# powerblade_test.net
KiCad netlist of a schematic drawn in EAGLE
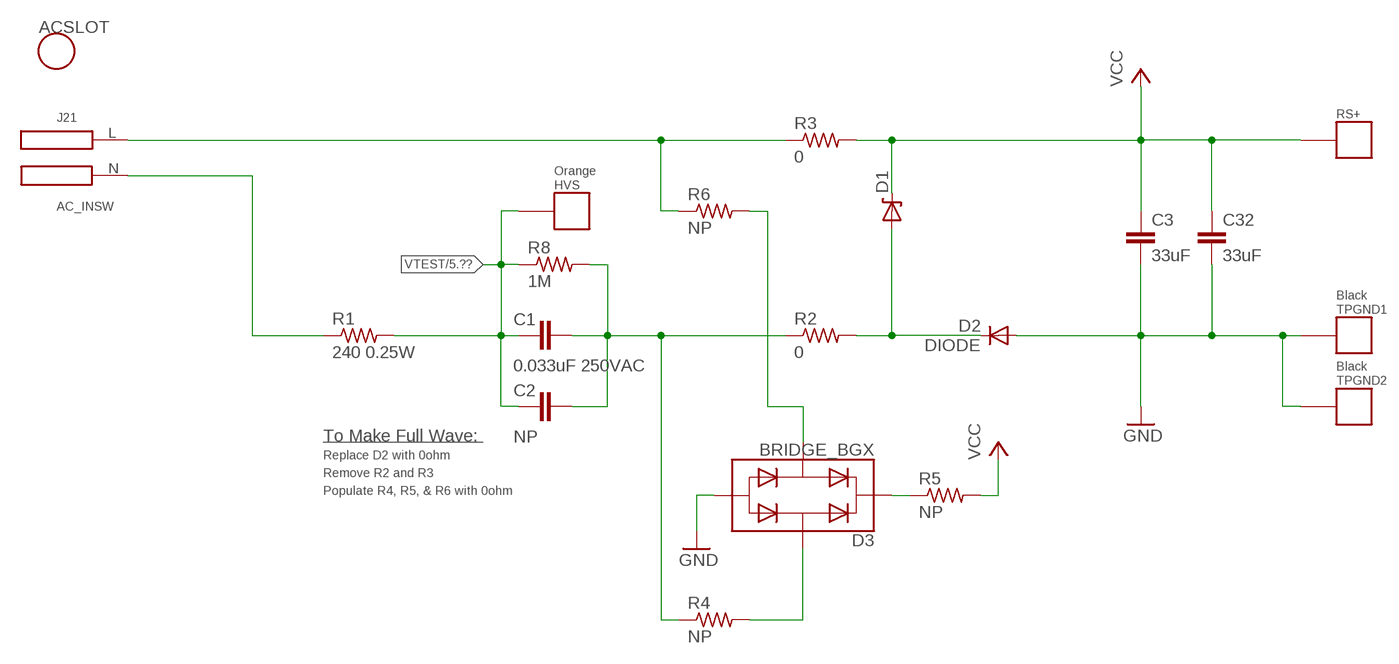
[diagram p0: schematic, sheet 1]
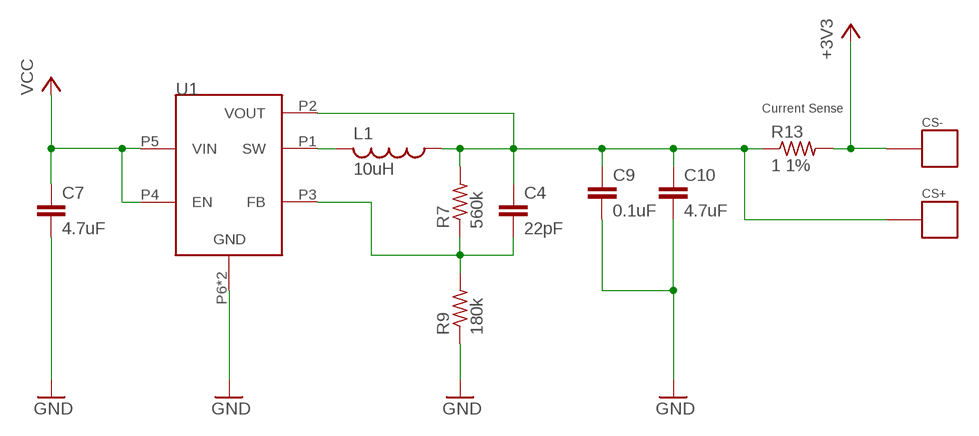
[diagram p1: schematic, sheet 2]
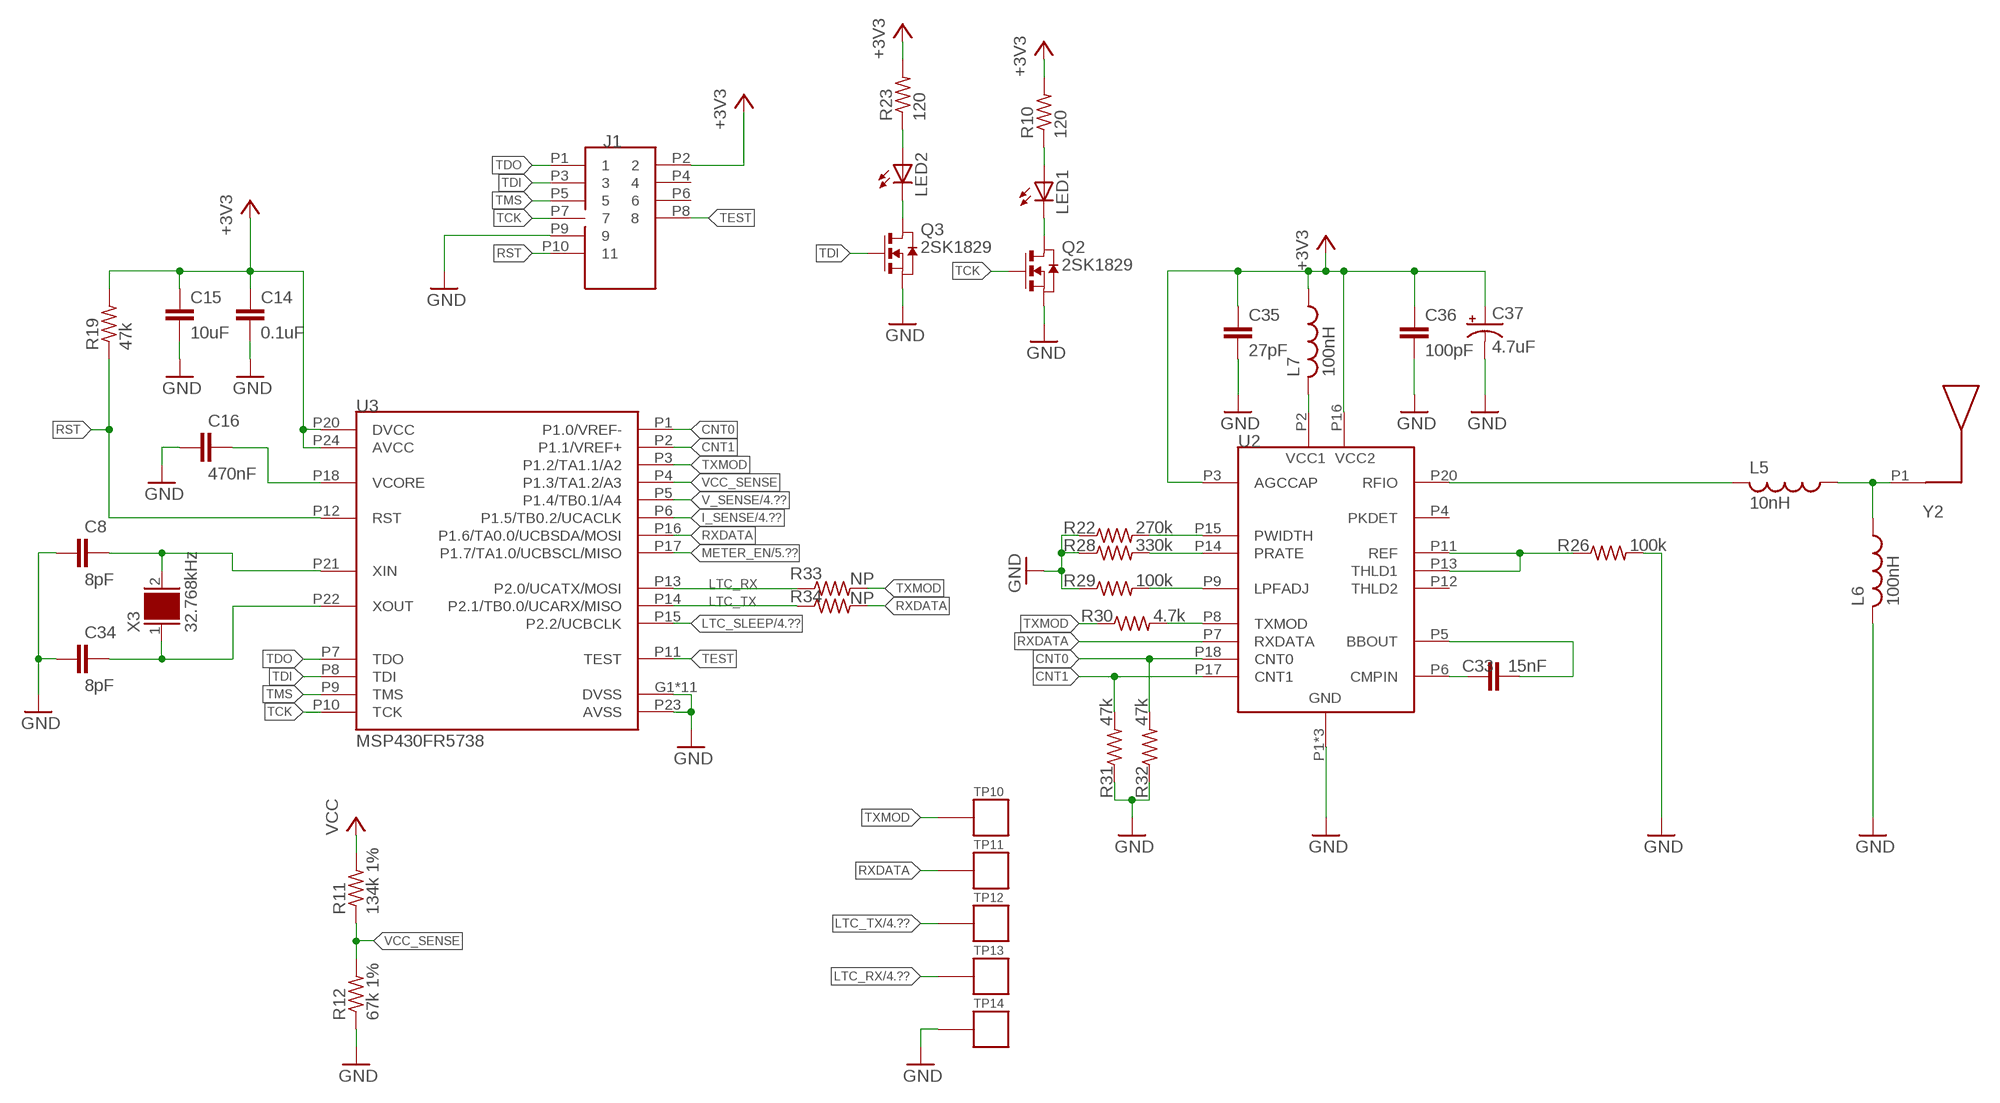
[diagram p2: schematic, sheet 3]
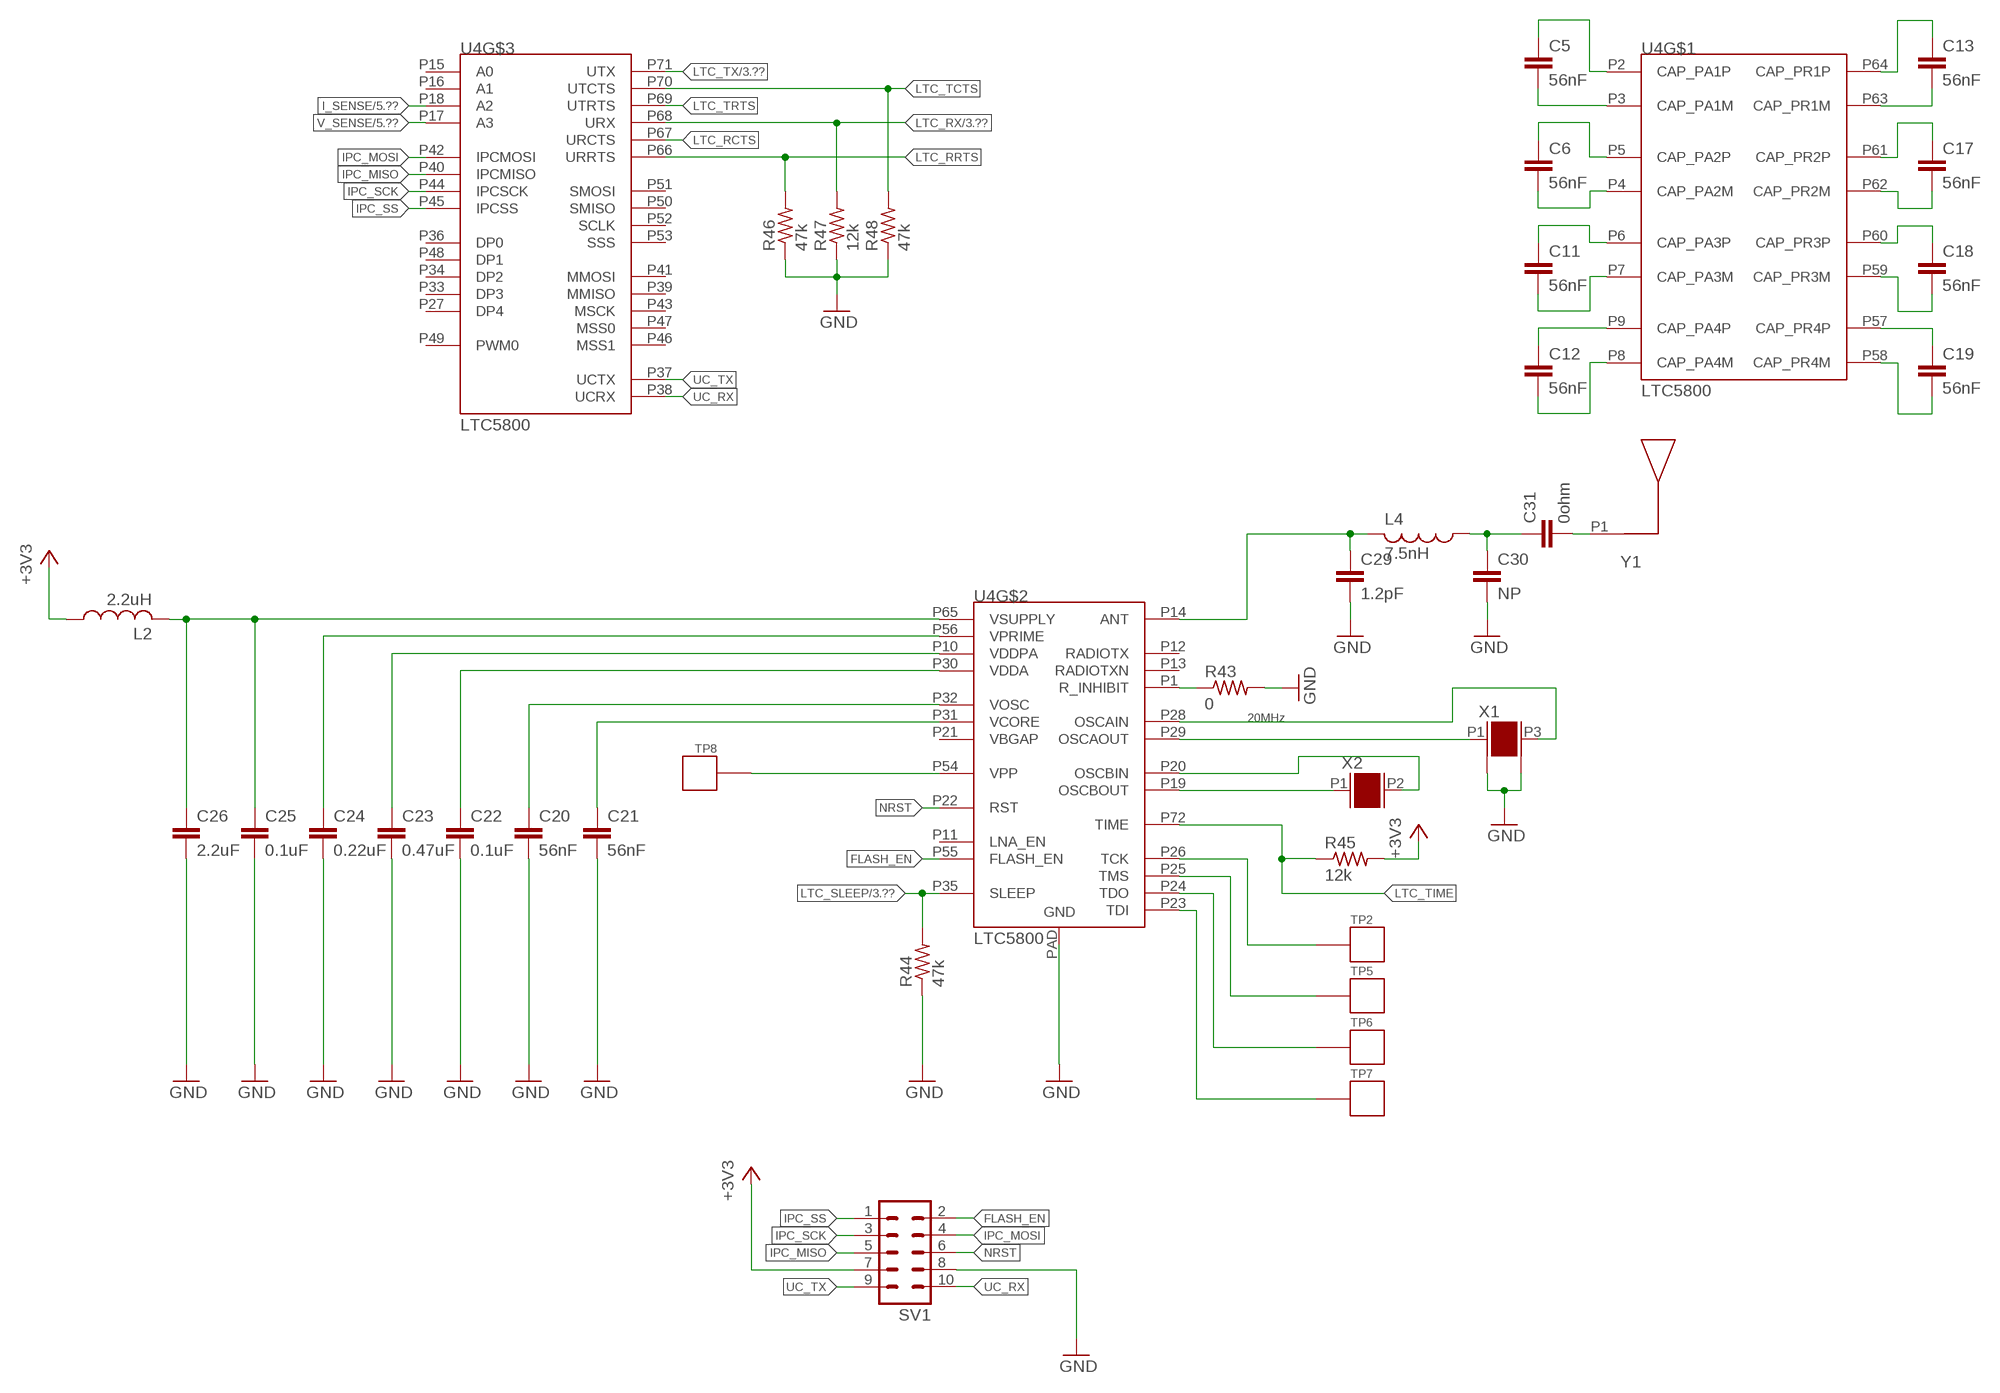
[diagram p3: schematic, sheet 4]
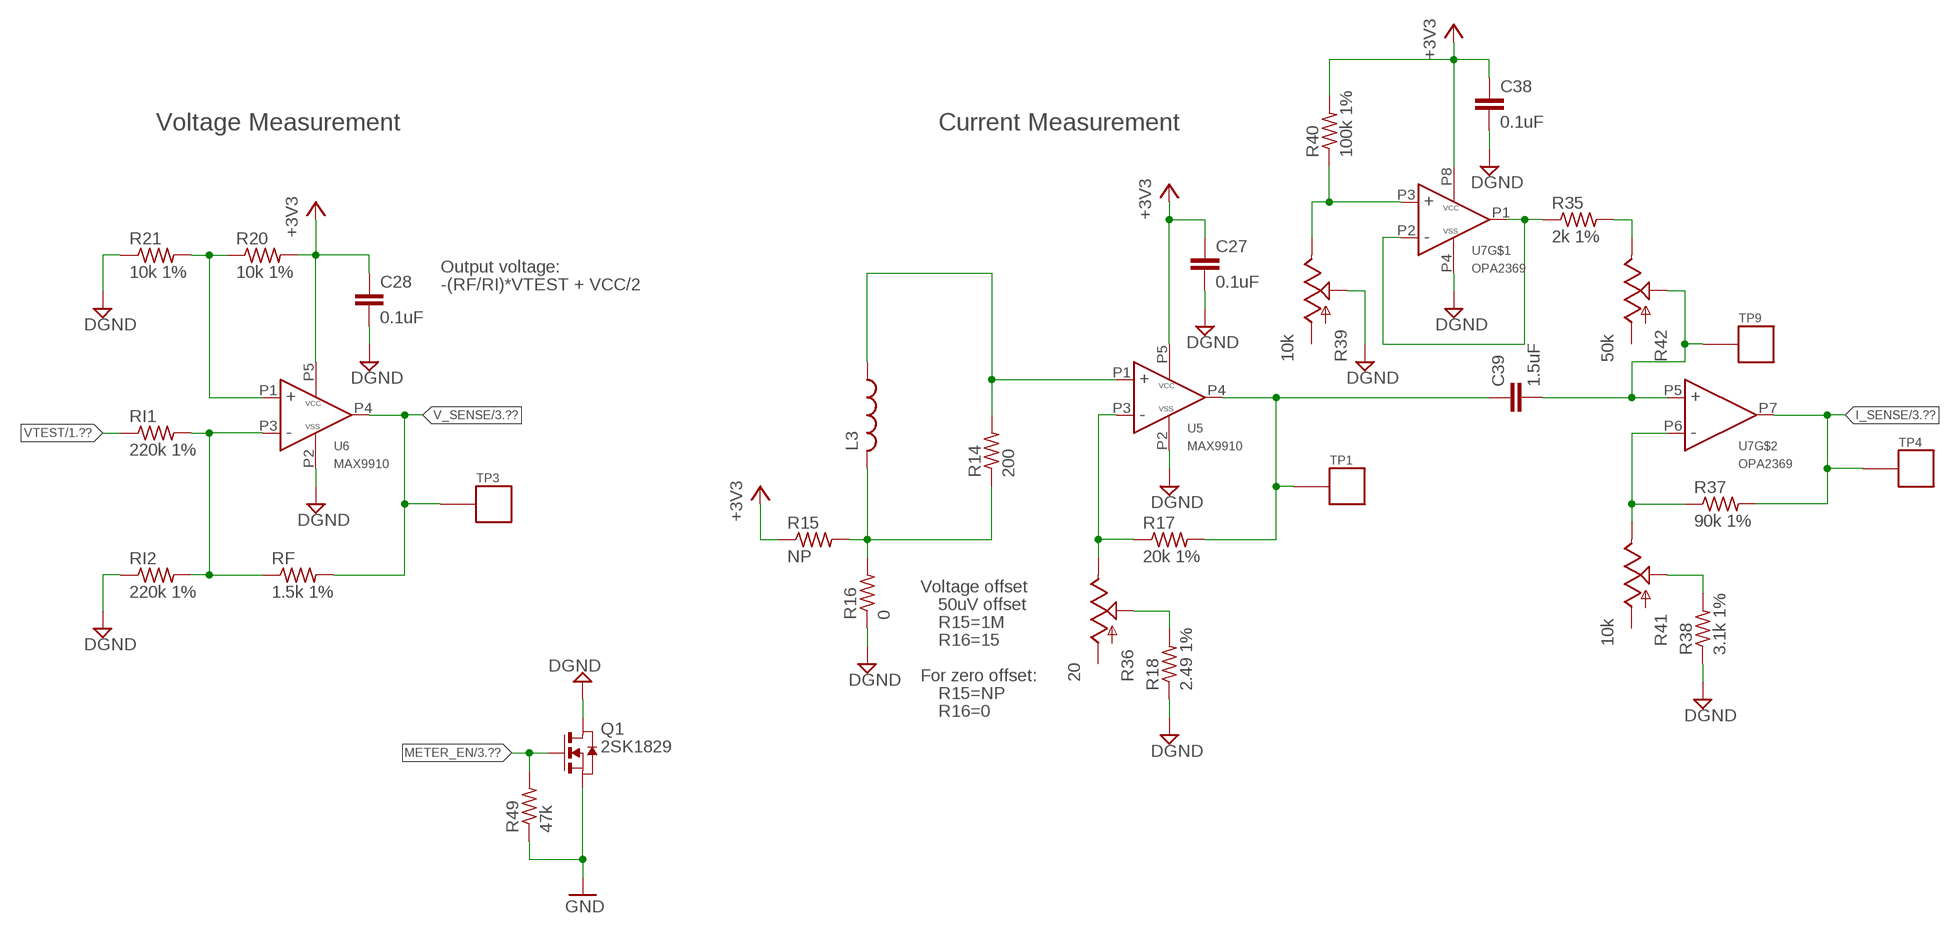
[diagram p4: schematic, sheet 5]

(export (version "E")
  (design (tool "Eeschema 10.0.6"))
  (components
    (comp (ref "C8")
      (value "8pF")
      (footprint "eagle-import:C0603")
      (libsource (lib "eagle-import") (part "C-EUC0603"))
    )
    (comp (ref "C14")
      (value "0.1uF")
      (footprint "eagle-import:C0603")
      (libsource (lib "eagle-import") (part "C-EUC0603"))
    )
    (comp (ref "C15")
      (value "10uF")
      (footprint "eagle-import:C0603")
      (libsource (lib "eagle-import") (part "C-EUC0603"))
    )
    (comp (ref "C16")
      (value "470nF")
      (footprint "eagle-import:C0603")
      (libsource (lib "eagle-import") (part "C-EUC0603"))
    )
    (comp (ref "C33")
      (value "15nF")
      (footprint "eagle-import:C0603")
      (libsource (lib "eagle-import") (part "C-EUC0603"))
    )
    (comp (ref "C34")
      (value "8pF")
      (footprint "eagle-import:C0603")
      (libsource (lib "eagle-import") (part "C-EUC0603"))
    )
    (comp (ref "C35")
      (value "27pF")
      (footprint "eagle-import:C0603")
      (libsource (lib "eagle-import") (part "C-EUC0603"))
    )
    (comp (ref "C36")
      (value "100pF")
      (footprint "eagle-import:C0603")
      (libsource (lib "eagle-import") (part "C-EUC0603"))
    )
    (comp (ref "C37")
      (value "4.7uF")
      (footprint "eagle-import:CPOL-0805")
      (libsource (lib "eagle-import") (part "CPOL-US0805"))
    )
    (comp (ref "J1")
      (value "JTAG_14PIN_IDC")
      (footprint "eagle-import:TC2050-IDC-430")
      (libsource (lib "eagle-import") (part "JTAG_14PIN_IDC"))
    )
    (comp (ref "L5")
      (value "10nH")
      (footprint "eagle-import:L0402")
      (libsource (lib "eagle-import") (part "L-USL0402"))
    )
    (comp (ref "L6")
      (value "100nH")
      (footprint "eagle-import:L0402")
      (libsource (lib "eagle-import") (part "L-USL0402"))
    )
    (comp (ref "L7")
      (value "100nH")
      (footprint "eagle-import:L0603")
      (libsource (lib "eagle-import") (part "L-USL0603"))
    )
    (comp (ref "LED1")
      (value "LED0603")
      (footprint "eagle-import:LED-0603")
      (libsource (lib "eagle-import") (part "LED0603"))
    )
    (comp (ref "LED2")
      (value "LED0603")
      (footprint "eagle-import:LED-0603")
      (libsource (lib "eagle-import") (part "LED0603"))
    )
    (comp (ref "Q2")
      (value "2SK1829")
      (footprint "eagle-import:SC-70-3")
      (libsource (lib "eagle-import") (part "2SK1829"))
    )
    (comp (ref "Q3")
      (value "2SK1829")
      (footprint "eagle-import:SC-70-3")
      (libsource (lib "eagle-import") (part "2SK1829"))
    )
    (comp (ref "R10")
      (value "120")
      (footprint "eagle-import:R0603")
      (libsource (lib "eagle-import") (part "R-US_R0603"))
    )
    (comp (ref "R11")
      (value "134k 1%")
      (footprint "eagle-import:R0603")
      (libsource (lib "eagle-import") (part "R-US_R0603"))
    )
    (comp (ref "R12")
      (value "67k 1%")
      (footprint "eagle-import:R0603")
      (libsource (lib "eagle-import") (part "R-US_R0603"))
    )
    (comp (ref "R19")
      (value "47k")
      (footprint "eagle-import:R0603")
      (libsource (lib "eagle-import") (part "R-US_R0603"))
    )
    (comp (ref "R22")
      (value "270k")
      (footprint "eagle-import:R0603")
      (libsource (lib "eagle-import") (part "R-US_R0603"))
    )
    (comp (ref "R23")
      (value "120")
      (footprint "eagle-import:R0603")
      (libsource (lib "eagle-import") (part "R-US_R0603"))
    )
    (comp (ref "R26")
      (value "100k")
      (footprint "eagle-import:R0603")
      (libsource (lib "eagle-import") (part "R-US_R0603"))
    )
    (comp (ref "R28")
      (value "330k")
      (footprint "eagle-import:R0603")
      (libsource (lib "eagle-import") (part "R-US_R0603"))
    )
    (comp (ref "R29")
      (value "100k")
      (footprint "eagle-import:R0603")
      (libsource (lib "eagle-import") (part "R-US_R0603"))
    )
    (comp (ref "R30")
      (value "4.7k")
      (footprint "eagle-import:R0603")
      (libsource (lib "eagle-import") (part "R-US_R0603"))
    )
    (comp (ref "R31")
      (value "47k")
      (footprint "eagle-import:R0603")
      (libsource (lib "eagle-import") (part "R-US_R0603"))
    )
    (comp (ref "R32")
      (value "47k")
      (footprint "eagle-import:R0603")
      (libsource (lib "eagle-import") (part "R-US_R0603"))
    )
    (comp (ref "R33")
      (value "NP")
      (footprint "eagle-import:R0603")
      (libsource (lib "eagle-import") (part "R-US_R0603"))
    )
    (comp (ref "R34")
      (value "NP")
      (footprint "eagle-import:R0603")
      (libsource (lib "eagle-import") (part "R-US_R0603"))
    )
    (comp (ref "TP10")
      (value "TP_STD")
      (footprint "eagle-import:TP")
      (libsource (lib "eagle-import") (part "TP_STD"))
    )
    (comp (ref "TP11")
      (value "TP_STD")
      (footprint "eagle-import:TP")
      (libsource (lib "eagle-import") (part "TP_STD"))
    )
    (comp (ref "TP12")
      (value "TP_STD")
      (footprint "eagle-import:TP")
      (libsource (lib "eagle-import") (part "TP_STD"))
    )
    (comp (ref "TP13")
      (value "TP_STD")
      (footprint "eagle-import:TP")
      (libsource (lib "eagle-import") (part "TP_STD"))
    )
    (comp (ref "TP14")
      (value "TP_STD")
      (footprint "eagle-import:TP")
      (libsource (lib "eagle-import") (part "TP_STD"))
    )
    (comp (ref "U2")
      (value "TR1000")
      (footprint "eagle-import:SM-20H")
      (libsource (lib "eagle-import") (part "TR1000"))
    )
    (comp (ref "U3")
      (value "MSP430FR5738")
      (footprint "eagle-import:VQFN-24")
      (libsource (lib "eagle-import") (part "MSP430FR5738"))
    )
    (comp (ref "X3")
      (value "32.768kHz")
      (footprint "eagle-import:0805")
      (libsource (lib "eagle-import") (part "CRYSTAL_0805"))
    )
    (comp (ref "Y2")
      (value "ANT-916")
      (footprint "eagle-import:ANT-916")
      (libsource (lib "eagle-import") (part "ANT-916"))
    )
    (comp (ref "C4")
      (value "22pF")
      (footprint "eagle-import:C0402")
      (libsource (lib "eagle-import") (part "C-EUC0402"))
    )
    (comp (ref "C7")
      (value "4.7uF")
      (footprint "eagle-import:C0603")
      (libsource (lib "eagle-import") (part "C-EUC0603"))
    )
    (comp (ref "C9")
      (value "0.1uF")
      (footprint "eagle-import:C0402")
      (libsource (lib "eagle-import") (part "C-EUC0402"))
    )
    (comp (ref "C10")
      (value "4.7uF")
      (footprint "eagle-import:C0402")
      (libsource (lib "eagle-import") (part "C-EUC0402"))
    )
    (comp (ref "CS+")
      (value "TP_MULT")
      (footprint "eagle-import:TP_MULT")
      (libsource (lib "eagle-import") (part "TP_MULT"))
    )
    (comp (ref "CS-")
      (value "TP_MULT")
      (footprint "eagle-import:TP_MULT")
      (libsource (lib "eagle-import") (part "TP_MULT"))
    )
    (comp (ref "L1")
      (value "10uH")
      (footprint "eagle-import:L0805")
      (libsource (lib "eagle-import") (part "L-USL0805"))
    )
    (comp (ref "R7")
      (value "560k")
      (footprint "eagle-import:R0402")
      (libsource (lib "eagle-import") (part "R-US_R0402"))
    )
    (comp (ref "R9")
      (value "180k")
      (footprint "eagle-import:R0402")
      (libsource (lib "eagle-import") (part "R-US_R0402"))
    )
    (comp (ref "R13")
      (value "1 1%")
      (footprint "eagle-import:R0603")
      (libsource (lib "eagle-import") (part "R-US_R0603"))
    )
    (comp (ref "U1")
      (value "TPS62122")
      (footprint "eagle-import:WDFN-6")
      (libsource (lib "eagle-import") (part "TPS62122"))
    )
    (comp (ref "ACSLOT")
      (value "AC_NODIM")
      (footprint "eagle-import:AC3_NODIM")
      (libsource (lib "eagle-import") (part "AC_NODIM"))
    )
    (comp (ref "C1")
      (value "0.033uF 250VAC")
      (footprint "eagle-import:C2220K")
      (libsource (lib "eagle-import") (part "C-EUC2220K"))
    )
    (comp (ref "C2")
      (value "NP")
      (footprint "eagle-import:C2220K")
      (libsource (lib "eagle-import") (part "C-EUC2220K"))
    )
    (comp (ref "C3")
      (value "33uF")
      (footprint "eagle-import:C0603")
      (libsource (lib "eagle-import") (part "C-EUC0603"))
    )
    (comp (ref "C32")
      (value "33uF")
      (footprint "eagle-import:C0603")
      (libsource (lib "eagle-import") (part "C-EUC0603"))
    )
    (comp (ref "D1")
      (value "ZENERBZT52")
      (footprint "eagle-import:BZT52")
      (fields (field (name "DIGIKEY") "NP"))
      (libsource (lib "eagle-import") (part "ZENERBZT52"))
    )
    (comp (ref "D2")
      (value "DIODE")
      (footprint "eagle-import:BAS521")
      (fields (field (name "DIGIKEY") "NP"))
      (libsource (lib "eagle-import") (part "DIODE"))
    )
    (comp (ref "D3")
      (value "BRIDGE_BGX")
      (footprint "eagle-import:TO-253-4")
      (fields (field (name "DIGIKEY") "NP"))
      (libsource (lib "eagle-import") (part "BRIDGE_BGX"))
    )
    (comp (ref "HVS")
      (value "TP_MULT")
      (footprint "eagle-import:TP_MULT")
      (libsource (lib "eagle-import") (part "TP_MULT"))
    )
    (comp (ref "J21")
      (value "AC_INSW")
      (footprint "eagle-import:AC_DC21")
      (fields (field (name "DIGIKEY") "NP"))
      (libsource (lib "eagle-import") (part "AC_INSW"))
    )
    (comp (ref "R1")
      (value "240 0.25W")
      (footprint "eagle-import:R0603")
      (libsource (lib "eagle-import") (part "R-US_R0603"))
    )
    (comp (ref "R2")
      (value "0")
      (footprint "eagle-import:R0603")
      (libsource (lib "eagle-import") (part "R-US_R0603"))
    )
    (comp (ref "R3")
      (value "0")
      (footprint "eagle-import:R0603")
      (libsource (lib "eagle-import") (part "R-US_R0603"))
    )
    (comp (ref "R4")
      (value "NP")
      (footprint "eagle-import:R0603")
      (libsource (lib "eagle-import") (part "R-US_R0603"))
    )
    (comp (ref "R5")
      (value "NP")
      (footprint "eagle-import:R0603")
      (libsource (lib "eagle-import") (part "R-US_R0603"))
    )
    (comp (ref "R6")
      (value "NP")
      (footprint "eagle-import:R0603")
      (libsource (lib "eagle-import") (part "R-US_R0603"))
    )
    (comp (ref "R8")
      (value "1M")
      (footprint "eagle-import:R0603")
      (libsource (lib "eagle-import") (part "R-US_R0603"))
    )
    (comp (ref "RS+")
      (value "TP_MULT")
      (footprint "eagle-import:TP_MULT")
      (libsource (lib "eagle-import") (part "TP_MULT"))
    )
    (comp (ref "TPGND1")
      (value "TP_MULT")
      (footprint "eagle-import:TP_MULT")
      (libsource (lib "eagle-import") (part "TP_MULT"))
    )
    (comp (ref "TPGND2")
      (value "TP_MULT")
      (footprint "eagle-import:TP_MULT")
      (libsource (lib "eagle-import") (part "TP_MULT"))
    )
    (comp (ref "C5")
      (value "56nF")
      (footprint "eagle-import:C0402")
      (libsource (lib "eagle-import") (part "C-EUC0402"))
    )
    (comp (ref "C6")
      (value "56nF")
      (footprint "eagle-import:C0402")
      (libsource (lib "eagle-import") (part "C-EUC0402"))
    )
    (comp (ref "C11")
      (value "56nF")
      (footprint "eagle-import:C0402")
      (libsource (lib "eagle-import") (part "C-EUC0402"))
    )
    (comp (ref "C12")
      (value "56nF")
      (footprint "eagle-import:C0402")
      (libsource (lib "eagle-import") (part "C-EUC0402"))
    )
    (comp (ref "C13")
      (value "56nF")
      (footprint "eagle-import:C0402")
      (libsource (lib "eagle-import") (part "C-EUC0402"))
    )
    (comp (ref "C17")
      (value "56nF")
      (footprint "eagle-import:C0402")
      (libsource (lib "eagle-import") (part "C-EUC0402"))
    )
    (comp (ref "C18")
      (value "56nF")
      (footprint "eagle-import:C0402")
      (libsource (lib "eagle-import") (part "C-EUC0402"))
    )
    (comp (ref "C19")
      (value "56nF")
      (footprint "eagle-import:C0402")
      (libsource (lib "eagle-import") (part "C-EUC0402"))
    )
    (comp (ref "C20")
      (value "56nF")
      (footprint "eagle-import:C0402")
      (libsource (lib "eagle-import") (part "C-EUC0402"))
    )
    (comp (ref "C21")
      (value "56nF")
      (footprint "eagle-import:C0402")
      (libsource (lib "eagle-import") (part "C-EUC0402"))
    )
    (comp (ref "C22")
      (value "0.1uF")
      (footprint "eagle-import:C0603")
      (libsource (lib "eagle-import") (part "C-EUC0603"))
    )
    (comp (ref "C23")
      (value "0.47uF")
      (footprint "eagle-import:C0603")
      (libsource (lib "eagle-import") (part "C-EUC0603"))
    )
    (comp (ref "C24")
      (value "0.22uF")
      (footprint "eagle-import:C0603")
      (libsource (lib "eagle-import") (part "C-EUC0603"))
    )
    (comp (ref "C25")
      (value "0.1uF")
      (footprint "eagle-import:C0603")
      (libsource (lib "eagle-import") (part "C-EUC0603"))
    )
    (comp (ref "C26")
      (value "2.2uF")
      (footprint "eagle-import:C0603")
      (libsource (lib "eagle-import") (part "C-EUC0603"))
    )
    (comp (ref "C29")
      (value "1.2pF")
      (footprint "eagle-import:C0402")
      (libsource (lib "eagle-import") (part "C-EUC0402"))
    )
    (comp (ref "C30")
      (value "NP")
      (footprint "eagle-import:C0402")
      (libsource (lib "eagle-import") (part "C-EUC0402"))
    )
    (comp (ref "C31")
      (value "0ohm")
      (footprint "eagle-import:C0402")
      (libsource (lib "eagle-import") (part "C-EUC0402"))
    )
    (comp (ref "L2")
      (value "2.2uH")
      (footprint "eagle-import:L0603")
      (libsource (lib "eagle-import") (part "L-USL0603"))
    )
    (comp (ref "L4")
      (value "7.5nH")
      (footprint "eagle-import:L0402")
      (libsource (lib "eagle-import") (part "L-USL0402"))
    )
    (comp (ref "R43")
      (value "0")
      (footprint "eagle-import:R0402")
      (libsource (lib "eagle-import") (part "R-US_R0402"))
    )
    (comp (ref "R44")
      (value "47k")
      (footprint "eagle-import:R0402")
      (libsource (lib "eagle-import") (part "R-US_R0402"))
    )
    (comp (ref "R45")
      (value "12k")
      (footprint "eagle-import:R0402")
      (libsource (lib "eagle-import") (part "R-US_R0402"))
    )
    (comp (ref "R46")
      (value "47k")
      (footprint "eagle-import:R0402")
      (libsource (lib "eagle-import") (part "R-US_R0402"))
    )
    (comp (ref "R47")
      (value "12k")
      (footprint "eagle-import:R0402")
      (libsource (lib "eagle-import") (part "R-US_R0402"))
    )
    (comp (ref "R48")
      (value "47k")
      (footprint "eagle-import:R0402")
      (libsource (lib "eagle-import") (part "R-US_R0402"))
    )
    (comp (ref "SV1")
      (value "MA05-2KEY")
      (footprint "eagle-import:MA05-2_KEY")
      (libsource (lib "eagle-import") (part "MA05-2KEY"))
    )
    (comp (ref "TP2")
      (value "TP_SMD")
      (footprint "eagle-import:TP_SMD")
      (libsource (lib "eagle-import") (part "TP_SMD"))
    )
    (comp (ref "TP5")
      (value "TP_SMD")
      (footprint "eagle-import:TP_SMD")
      (libsource (lib "eagle-import") (part "TP_SMD"))
    )
    (comp (ref "TP6")
      (value "TP_SMD")
      (footprint "eagle-import:TP_SMD")
      (libsource (lib "eagle-import") (part "TP_SMD"))
    )
    (comp (ref "TP7")
      (value "TP_SMD")
      (footprint "eagle-import:TP_SMD")
      (libsource (lib "eagle-import") (part "TP_SMD"))
    )
    (comp (ref "TP8")
      (value "TP_STD")
      (footprint "eagle-import:TP")
      (libsource (lib "eagle-import") (part "TP_STD"))
    )
    (comp (ref "U4")
      (value "LTC5800")
      (footprint "eagle-import:QFN-72")
      (libsource (lib "eagle-import") (part "LTC5800"))
    )
    (comp (ref "X1")
      (value "ABM8G")
      (footprint "eagle-import:ABM8G")
      (libsource (lib "eagle-import") (part "ABM8G"))
    )
    (comp (ref "X2")
      (value "ABS07")
      (footprint "eagle-import:ABS07")
      (libsource (lib "eagle-import") (part "ABS07"))
    )
    (comp (ref "Y1")
      (value "UREACH_XTEND")
      (footprint "eagle-import:UREACH_XTEND")
      (libsource (lib "eagle-import") (part "UREACH_XTEND"))
    )
    (comp (ref "C27")
      (value "0.1uF")
      (footprint "eagle-import:C0402")
      (libsource (lib "eagle-import") (part "C-EUC0402"))
    )
    (comp (ref "C28")
      (value "0.1uF")
      (footprint "eagle-import:C0402")
      (libsource (lib "eagle-import") (part "C-EUC0402"))
    )
    (comp (ref "C38")
      (value "0.1uF")
      (footprint "eagle-import:C0402")
      (libsource (lib "eagle-import") (part "C-EUC0402"))
    )
    (comp (ref "C39")
      (value "1.5uF")
      (footprint "eagle-import:C0402")
      (libsource (lib "eagle-import") (part "C-EUC0402"))
    )
    (comp (ref "L3")
      (value "L-USL0805")
      (footprint "eagle-import:L0805")
      (libsource (lib "eagle-import") (part "L-USL0805"))
    )
    (comp (ref "Q1")
      (value "2SK1829")
      (footprint "eagle-import:SC-70-3")
      (libsource (lib "eagle-import") (part "2SK1829"))
    )
    (comp (ref "R14")
      (value "200")
      (footprint "eagle-import:R0402")
      (libsource (lib "eagle-import") (part "R-US_R0402"))
    )
    (comp (ref "R15")
      (value "NP")
      (footprint "eagle-import:R0402")
      (libsource (lib "eagle-import") (part "R-US_R0402"))
    )
    (comp (ref "R16")
      (value "0")
      (footprint "eagle-import:R0402")
      (libsource (lib "eagle-import") (part "R-US_R0402"))
    )
    (comp (ref "R17")
      (value "20k 1%")
      (footprint "eagle-import:R0402")
      (libsource (lib "eagle-import") (part "R-US_R0402"))
    )
    (comp (ref "R18")
      (value "2.49 1%")
      (footprint "eagle-import:R0402")
      (libsource (lib "eagle-import") (part "R-US_R0402"))
    )
    (comp (ref "R20")
      (value "10k 1%")
      (footprint "eagle-import:R0402")
      (libsource (lib "eagle-import") (part "R-US_R0402"))
    )
    (comp (ref "R21")
      (value "10k 1%")
      (footprint "eagle-import:R0402")
      (libsource (lib "eagle-import") (part "R-US_R0402"))
    )
    (comp (ref "R35")
      (value "2k 1%")
      (footprint "eagle-import:R0402")
      (libsource (lib "eagle-import") (part "R-US_R0402"))
    )
    (comp (ref "R36")
      (value "20")
      (footprint "eagle-import:3313_POT")
      (libsource (lib "eagle-import") (part "3313_POT"))
    )
    (comp (ref "R37")
      (value "90k 1%")
      (footprint "eagle-import:R0402")
      (libsource (lib "eagle-import") (part "R-US_R0402"))
    )
    (comp (ref "R38")
      (value "3.1k 1%")
      (footprint "eagle-import:R0603")
      (libsource (lib "eagle-import") (part "R-US_R0603"))
    )
    (comp (ref "R39")
      (value "10k")
      (footprint "eagle-import:3313_POT")
      (libsource (lib "eagle-import") (part "3313_POT"))
    )
    (comp (ref "R40")
      (value "100k 1%")
      (footprint "eagle-import:R0402")
      (libsource (lib "eagle-import") (part "R-US_R0402"))
    )
    (comp (ref "R41")
      (value "10k")
      (footprint "eagle-import:3313_POT")
      (libsource (lib "eagle-import") (part "3313_POT"))
    )
    (comp (ref "R42")
      (value "50k")
      (footprint "eagle-import:3313_POT")
      (libsource (lib "eagle-import") (part "3313_POT"))
    )
    (comp (ref "R49")
      (value "47k")
      (footprint "eagle-import:R0603")
      (libsource (lib "eagle-import") (part "R-US_R0603"))
    )
    (comp (ref "RF")
      (value "1.5k 1%")
      (footprint "eagle-import:R0402")
      (libsource (lib "eagle-import") (part "R-US_R0402"))
    )
    (comp (ref "RI1")
      (value "220k 1%")
      (footprint "eagle-import:R0402")
      (libsource (lib "eagle-import") (part "R-US_R0402"))
    )
    (comp (ref "RI2")
      (value "220k 1%")
      (footprint "eagle-import:R0402")
      (libsource (lib "eagle-import") (part "R-US_R0402"))
    )
    (comp (ref "TP1")
      (value "TP_MULT")
      (footprint "eagle-import:TP_MULT")
      (libsource (lib "eagle-import") (part "TP_MULT"))
    )
    (comp (ref "TP3")
      (value "TP_MULT")
      (footprint "eagle-import:TP_MULT")
      (libsource (lib "eagle-import") (part "TP_MULT"))
    )
    (comp (ref "TP4")
      (value "TP_MULT")
      (footprint "eagle-import:TP_MULT")
      (libsource (lib "eagle-import") (part "TP_MULT"))
    )
    (comp (ref "TP9")
      (value "TP_MULT")
      (footprint "eagle-import:TP_MULT")
      (libsource (lib "eagle-import") (part "TP_MULT"))
    )
    (comp (ref "U5")
      (value "MAX9910")
      (footprint "eagle-import:SC70-5")
      (libsource (lib "eagle-import") (part "MAX9910"))
    )
    (comp (ref "U6")
      (value "MAX9910")
      (footprint "eagle-import:SC70-5")
      (libsource (lib "eagle-import") (part "MAX9910"))
    )
    (comp (ref "U7")
      (value "OPA2369")
      (footprint "eagle-import:SOT-23-8")
      (libsource (lib "eagle-import") (part "OPA2369"))
    )
  )
  (nets
    (net (code "1") (name "+3V3") (class "Default")
      (node (ref "C14") (pin "1") (pinfunction "1_1") (pintype "passive"))
      (node (ref "C15") (pin "1") (pinfunction "1_1") (pintype "passive"))
      (node (ref "C27") (pin "1") (pinfunction "1_1") (pintype "passive"))
      (node (ref "C28") (pin "1") (pinfunction "1_1") (pintype "passive"))
      (node (ref "C35") (pin "1") (pinfunction "1_1") (pintype "passive"))
      (node (ref "C36") (pin "1") (pinfunction "1_1") (pintype "passive"))
      (node (ref "C37") (pin "+") (pinfunction "+_+") (pintype "passive"))
      (node (ref "C38") (pin "1") (pinfunction "1_1") (pintype "passive"))
      (node (ref "CS-") (pin "P$1") (pinfunction "P$1_P$1") (pintype "bidirectional"))
      (node (ref "J1") (pin "P2") (pinfunction "2_P2") (pintype "bidirectional"))
      (node (ref "L2") (pin "1") (pinfunction "1_1") (pintype "passive"))
      (node (ref "L7") (pin "1") (pinfunction "1_1") (pintype "passive"))
      (node (ref "R10") (pin "2") (pinfunction "2_2") (pintype "passive"))
      (node (ref "R13") (pin "2") (pinfunction "2_2") (pintype "passive"))
      (node (ref "R15") (pin "1") (pinfunction "1_1") (pintype "passive"))
      (node (ref "R19") (pin "2") (pinfunction "2_2") (pintype "passive"))
      (node (ref "R20") (pin "2") (pinfunction "2_2") (pintype "passive"))
      (node (ref "R23") (pin "2") (pinfunction "2_2") (pintype "passive"))
      (node (ref "R40") (pin "2") (pinfunction "2_2") (pintype "passive"))
      (node (ref "R45") (pin "2") (pinfunction "2_2") (pintype "passive"))
      (node (ref "SV1") (pin "7") (pinfunction "7_7") (pintype "passive"))
      (node (ref "U2") (pin "P16") (pinfunction "VCC2_P16") (pintype "bidirectional"))
      (node (ref "U2") (pin "P3") (pinfunction "AGCCAP_P3") (pintype "bidirectional"))
      (node (ref "U3") (pin "P20") (pinfunction "DVCC_P20") (pintype "bidirectional"))
      (node (ref "U3") (pin "P24") (pinfunction "AVCC_P24") (pintype "bidirectional"))
      (node (ref "U5") (pin "P5") (pinfunction "VCC_P5") (pintype "bidirectional"))
      (node (ref "U6") (pin "P5") (pinfunction "VCC_P5") (pintype "bidirectional"))
      (node (ref "U7") (pin "P8") (pinfunction "VCC_P8") (pintype "bidirectional"))
    )
    (net (code "2") (name "CNT0") (class "Default")
      (node (ref "R32") (pin "2") (pinfunction "2_2") (pintype "passive"))
      (node (ref "U2") (pin "P18") (pinfunction "CNT0_P18") (pintype "bidirectional"))
      (node (ref "U3") (pin "P1") (pinfunction "P1.0/VREF-_P1") (pintype "bidirectional"))
    )
    (net (code "3") (name "CNT1") (class "Default")
      (node (ref "R31") (pin "2") (pinfunction "2_2") (pintype "passive"))
      (node (ref "U2") (pin "P17") (pinfunction "CNT1_P17") (pintype "bidirectional"))
      (node (ref "U3") (pin "P2") (pinfunction "P1.1/VREF+_P2") (pintype "bidirectional"))
    )
    (net (code "4") (name "DGND") (class "Default")
      (node (ref "C27") (pin "2") (pinfunction "2_2") (pintype "passive"))
      (node (ref "C28") (pin "2") (pinfunction "2_2") (pintype "passive"))
      (node (ref "C38") (pin "2") (pinfunction "2_2") (pintype "passive"))
      (node (ref "Q1") (pin "P3") (pinfunction "D_P3") (pintype "passive"))
      (node (ref "R16") (pin "1") (pinfunction "1_1") (pintype "passive"))
      (node (ref "R18") (pin "1") (pinfunction "1_1") (pintype "passive"))
      (node (ref "R21") (pin "1") (pinfunction "1_1") (pintype "passive"))
      (node (ref "R38") (pin "1") (pinfunction "1_1") (pintype "passive"))
      (node (ref "R39") (pin "PW") (pinfunction "PW_PW") (pintype "passive"))
      (node (ref "RI2") (pin "1") (pinfunction "1_1") (pintype "passive"))
      (node (ref "U5") (pin "P2") (pinfunction "VSS_P2") (pintype "bidirectional"))
      (node (ref "U6") (pin "P2") (pinfunction "VSS_P2") (pintype "bidirectional"))
      (node (ref "U7") (pin "P4") (pinfunction "VSS_P4") (pintype "bidirectional"))
    )
    (net (code "5") (name "FLASH_EN") (class "Default")
      (node (ref "SV1") (pin "2") (pinfunction "2_2") (pintype "passive"))
      (node (ref "U4") (pin "P55") (pinfunction "FLASH_EN_P55") (pintype "bidirectional"))
    )
    (net (code "6") (name "GND") (class "Default")
      (node (ref "C10") (pin "2") (pinfunction "2_2") (pintype "passive"))
      (node (ref "C14") (pin "2") (pinfunction "2_2") (pintype "passive"))
      (node (ref "C15") (pin "2") (pinfunction "2_2") (pintype "passive"))
      (node (ref "C16") (pin "1") (pinfunction "1_1") (pintype "passive"))
      (node (ref "C20") (pin "2") (pinfunction "2_2") (pintype "passive"))
      (node (ref "C21") (pin "2") (pinfunction "2_2") (pintype "passive"))
      (node (ref "C22") (pin "2") (pinfunction "2_2") (pintype "passive"))
      (node (ref "C23") (pin "2") (pinfunction "2_2") (pintype "passive"))
      (node (ref "C24") (pin "2") (pinfunction "2_2") (pintype "passive"))
      (node (ref "C25") (pin "2") (pinfunction "2_2") (pintype "passive"))
      (node (ref "C26") (pin "2") (pinfunction "2_2") (pintype "passive"))
      (node (ref "C29") (pin "2") (pinfunction "2_2") (pintype "passive"))
      (node (ref "C3") (pin "2") (pinfunction "2_2") (pintype "passive"))
      (node (ref "C30") (pin "2") (pinfunction "2_2") (pintype "passive"))
      (node (ref "C32") (pin "2") (pinfunction "2_2") (pintype "passive"))
      (node (ref "C34") (pin "1") (pinfunction "1_1") (pintype "passive"))
      (node (ref "C35") (pin "2") (pinfunction "2_2") (pintype "passive"))
      (node (ref "C36") (pin "2") (pinfunction "2_2") (pintype "passive"))
      (node (ref "C37") (pin "-") (pinfunction "-_-") (pintype "passive"))
      (node (ref "C7") (pin "2") (pinfunction "2_2") (pintype "passive"))
      (node (ref "C8") (pin "1") (pinfunction "1_1") (pintype "passive"))
      (node (ref "C9") (pin "2") (pinfunction "2_2") (pintype "passive"))
      (node (ref "D2") (pin "A") (pinfunction "A_A") (pintype "passive"))
      (node (ref "D3") (pin "P3") (pinfunction "P3_P3") (pintype "passive"))
      (node (ref "J1") (pin "P9") (pinfunction "9_P9") (pintype "bidirectional"))
      (node (ref "L6") (pin "2") (pinfunction "2_2") (pintype "passive"))
      (node (ref "Q1") (pin "P2") (pinfunction "S_P2") (pintype "passive"))
      (node (ref "Q2") (pin "P2") (pinfunction "S_P2") (pintype "passive"))
      (node (ref "Q3") (pin "P2") (pinfunction "S_P2") (pintype "passive"))
      (node (ref "R12") (pin "1") (pinfunction "1_1") (pintype "passive"))
      (node (ref "R22") (pin "1") (pinfunction "1_1") (pintype "passive"))
      (node (ref "R26") (pin "2") (pinfunction "2_2") (pintype "passive"))
      (node (ref "R28") (pin "1") (pinfunction "1_1") (pintype "passive"))
      (node (ref "R29") (pin "1") (pinfunction "1_1") (pintype "passive"))
      (node (ref "R31") (pin "1") (pinfunction "1_1") (pintype "passive"))
      (node (ref "R32") (pin "1") (pinfunction "1_1") (pintype "passive"))
      (node (ref "R43") (pin "2") (pinfunction "2_2") (pintype "passive"))
      (node (ref "R44") (pin "1") (pinfunction "1_1") (pintype "passive"))
      (node (ref "R46") (pin "1") (pinfunction "1_1") (pintype "passive"))
      (node (ref "R47") (pin "1") (pinfunction "1_1") (pintype "passive"))
      (node (ref "R48") (pin "1") (pinfunction "1_1") (pintype "passive"))
      (node (ref "R49") (pin "1") (pinfunction "1_1") (pintype "passive"))
      (node (ref "R9") (pin "1") (pinfunction "1_1") (pintype "passive"))
      (node (ref "SV1") (pin "8") (pinfunction "8_8") (pintype "passive"))
      (node (ref "TP14") (pin "P$1") (pinfunction "P$1_P$1") (pintype "bidirectional"))
      (node (ref "TPGND1") (pin "P$1") (pinfunction "P$1_P$1") (pintype "bidirectional"))
      (node (ref "TPGND2") (pin "P$1") (pinfunction "P$1_P$1") (pintype "bidirectional"))
      (node (ref "U1") (pin "P6") (pinfunction "GND_P6") (pintype "bidirectional"))
      (node (ref "U1") (pin "PAD") (pinfunction "GND_PAD") (pintype "bidirectional"))
      (node (ref "U2") (pin "P1") (pinfunction "GND_P1") (pintype "bidirectional"))
      (node (ref "U2") (pin "P10") (pinfunction "GND_P10") (pintype "bidirectional"))
      (node (ref "U2") (pin "P19") (pinfunction "GND_P19") (pintype "bidirectional"))
      (node (ref "U3") (pin "G1") (pinfunction "DVSS_G1") (pintype "bidirectional"))
      (node (ref "U3") (pin "G2") (pinfunction "DVSS_G2") (pintype "bidirectional"))
      (node (ref "U3") (pin "G3") (pinfunction "DVSS_G3") (pintype "bidirectional"))
      (node (ref "U3") (pin "G4") (pinfunction "DVSS_G4") (pintype "bidirectional"))
      (node (ref "U3") (pin "G5") (pinfunction "DVSS_G5") (pintype "bidirectional"))
      (node (ref "U3") (pin "G6") (pinfunction "DVSS_G6") (pintype "bidirectional"))
      (node (ref "U3") (pin "G7") (pinfunction "DVSS_G7") (pintype "bidirectional"))
      (node (ref "U3") (pin "G8") (pinfunction "DVSS_G8") (pintype "bidirectional"))
      (node (ref "U3") (pin "G9") (pinfunction "DVSS_G9") (pintype "bidirectional"))
      (node (ref "U3") (pin "P19") (pinfunction "DVSS_P19") (pintype "bidirectional"))
      (node (ref "U3") (pin "P23") (pinfunction "AVSS_P23") (pintype "bidirectional"))
      (node (ref "U3") (pin "PAD") (pinfunction "DVSS_PAD") (pintype "bidirectional"))
      (node (ref "U4") (pin "PAD") (pinfunction "GND_PAD") (pintype "bidirectional"))
      (node (ref "X1") (pin "P2") (pinfunction "G1_P2") (pintype "bidirectional"))
      (node (ref "X1") (pin "P4") (pinfunction "G2_P4") (pintype "bidirectional"))
    )
    (net (code "7") (name "IPC_MISO") (class "Default")
      (node (ref "SV1") (pin "5") (pinfunction "5_5") (pintype "passive"))
      (node (ref "U4") (pin "P40") (pinfunction "IPCMISO_P40") (pintype "bidirectional"))
    )
    (net (code "8") (name "IPC_MOSI") (class "Default")
      (node (ref "SV1") (pin "4") (pinfunction "4_4") (pintype "passive"))
      (node (ref "U4") (pin "P42") (pinfunction "IPCMOSI_P42") (pintype "bidirectional"))
    )
    (net (code "9") (name "IPC_SCK") (class "Default")
      (node (ref "SV1") (pin "3") (pinfunction "3_3") (pintype "passive"))
      (node (ref "U4") (pin "P44") (pinfunction "IPCSCK_P44") (pintype "bidirectional"))
    )
    (net (code "10") (name "IPC_SS") (class "Default")
      (node (ref "SV1") (pin "1") (pinfunction "1_1") (pintype "passive"))
      (node (ref "U4") (pin "P45") (pinfunction "IPCSS_P45") (pintype "bidirectional"))
    )
    (net (code "11") (name "I_SENSE") (class "Default")
      (node (ref "R37") (pin "2") (pinfunction "2_2") (pintype "passive"))
      (node (ref "TP4") (pin "P$1") (pinfunction "P$1_P$1") (pintype "bidirectional"))
      (node (ref "U3") (pin "P6") (pinfunction "P1.5/TB0.2/UCACLK_P6") (pintype "bidirectional"))
      (node (ref "U4") (pin "P18") (pinfunction "A2_P18") (pintype "bidirectional"))
      (node (ref "U7") (pin "P7") (pinfunction "OUT_P7") (pintype "bidirectional"))
    )
    (net (code "12") (name "LTC_RCTS") (class "Default")
      (node (ref "U4") (pin "P67") (pinfunction "URCTS_P67") (pintype "bidirectional"))
    )
    (net (code "13") (name "LTC_RRTS") (class "Default")
      (node (ref "R46") (pin "2") (pinfunction "2_2") (pintype "passive"))
      (node (ref "U4") (pin "P66") (pinfunction "URRTS_P66") (pintype "bidirectional"))
    )
    (net (code "14") (name "LTC_RX") (class "Default")
      (node (ref "R33") (pin "1") (pinfunction "1_1") (pintype "passive"))
      (node (ref "R47") (pin "2") (pinfunction "2_2") (pintype "passive"))
      (node (ref "TP13") (pin "P$1") (pinfunction "P$1_P$1") (pintype "bidirectional"))
      (node (ref "U3") (pin "P13") (pinfunction "P2.0/UCATX/MOSI_P13") (pintype "bidirectional"))
      (node (ref "U4") (pin "P68") (pinfunction "URX_P68") (pintype "bidirectional"))
    )
    (net (code "15") (name "LTC_SLEEP") (class "Default")
      (node (ref "R44") (pin "2") (pinfunction "2_2") (pintype "passive"))
      (node (ref "U3") (pin "P15") (pinfunction "P2.2/UCBCLK_P15") (pintype "bidirectional"))
      (node (ref "U4") (pin "P35") (pinfunction "SLEEP_P35") (pintype "bidirectional"))
    )
    (net (code "16") (name "LTC_TCTS") (class "Default")
      (node (ref "R48") (pin "2") (pinfunction "2_2") (pintype "passive"))
      (node (ref "U4") (pin "P70") (pinfunction "UTCTS_P70") (pintype "bidirectional"))
    )
    (net (code "17") (name "LTC_TIME") (class "Default")
      (node (ref "R45") (pin "1") (pinfunction "1_1") (pintype "passive"))
      (node (ref "U4") (pin "P72") (pinfunction "TIME_P72") (pintype "bidirectional"))
    )
    (net (code "18") (name "LTC_TRTS") (class "Default")
      (node (ref "U4") (pin "P69") (pinfunction "UTRTS_P69") (pintype "bidirectional"))
    )
    (net (code "19") (name "LTC_TX") (class "Default")
      (node (ref "R34") (pin "1") (pinfunction "1_1") (pintype "passive"))
      (node (ref "TP12") (pin "P$1") (pinfunction "P$1_P$1") (pintype "bidirectional"))
      (node (ref "U3") (pin "P14") (pinfunction "P2.1/TB0.0/UCARX/MISO_P14") (pintype "bidirectional"))
      (node (ref "U4") (pin "P71") (pinfunction "UTX_P71") (pintype "bidirectional"))
    )
    (net (code "20") (name "METER_EN") (class "Default")
      (node (ref "Q1") (pin "P1") (pinfunction "G_P1") (pintype "passive"))
      (node (ref "R49") (pin "2") (pinfunction "2_2") (pintype "passive"))
      (node (ref "U3") (pin "P17") (pinfunction "P1.7/TA1.0/UCBSCL/MISO_P17") (pintype "bidirectional"))
    )
    (net (code "21") (name "NRST") (class "Default")
      (node (ref "SV1") (pin "6") (pinfunction "6_6") (pintype "passive"))
      (node (ref "U4") (pin "P22") (pinfunction "RST_P22") (pintype "bidirectional"))
    )
    (net (code "22") (name "Net-(C1-Pad1)") (class "Default")
      (node (ref "C1") (pin "1") (pinfunction "1_1") (pintype "passive"))
      (node (ref "C2") (pin "1") (pinfunction "1_1") (pintype "passive"))
      (node (ref "R2") (pin "1") (pinfunction "1_1") (pintype "passive"))
      (node (ref "R4") (pin "1") (pinfunction "1_1") (pintype "passive"))
      (node (ref "R8") (pin "2") (pinfunction "2_2") (pintype "passive"))
    )
    (net (code "23") (name "Net-(C30-Pad1)") (class "Default")
      (node (ref "C30") (pin "1") (pinfunction "1_1") (pintype "passive"))
      (node (ref "C31") (pin "1") (pinfunction "1_1") (pintype "passive"))
      (node (ref "L4") (pin "1") (pinfunction "1_1") (pintype "passive"))
    )
    (net (code "24") (name "Net-(C31-Pad2)") (class "Default")
      (node (ref "C31") (pin "2") (pinfunction "2_2") (pintype "passive"))
      (node (ref "Y1") (pin "P1") (pinfunction "P1_P1") (pintype "bidirectional"))
    )
    (net (code "25") (name "Net-(D1-PadA)") (class "Default")
      (node (ref "D1") (pin "A") (pinfunction "A_A") (pintype "passive"))
      (node (ref "D2") (pin "C") (pinfunction "C_C") (pintype "passive"))
      (node (ref "R2") (pin "2") (pinfunction "2_2") (pintype "passive"))
    )
    (net (code "26") (name "Net-(D3-PadP1)") (class "Default")
      (node (ref "D3") (pin "P1") (pinfunction "P1_P1") (pintype "passive"))
      (node (ref "R5") (pin "1") (pinfunction "1_1") (pintype "passive"))
    )
    (net (code "27") (name "Net-(D3-PadP2)") (class "Default")
      (node (ref "D3") (pin "P2") (pinfunction "P2_P2") (pintype "passive"))
      (node (ref "R6") (pin "2") (pinfunction "2_2") (pintype "passive"))
    )
    (net (code "28") (name "Net-(D3-PadP4)") (class "Default")
      (node (ref "D3") (pin "P4") (pinfunction "P4_P4") (pintype "passive"))
      (node (ref "R4") (pin "2") (pinfunction "2_2") (pintype "passive"))
    )
    (net (code "29") (name "Net-(J21-P)") (class "Default")
      (node (ref "J21") (pin "L") (pinfunction "P_L") (pintype "bidirectional"))
      (node (ref "R3") (pin "1") (pinfunction "1_1") (pintype "passive"))
      (node (ref "R6") (pin "1") (pinfunction "1_1") (pintype "passive"))
    )
    (net (code "30") (name "Net-(J21-PadN)") (class "Default")
      (node (ref "J21") (pin "N") (pinfunction "N_N") (pintype "bidirectional"))
      (node (ref "R1") (pin "1") (pinfunction "1_1") (pintype "passive"))
    )
    (net (code "31") (name "Net-(L3-Pad2)") (class "Default")
      (node (ref "L3") (pin "2") (pinfunction "2_2") (pintype "passive"))
      (node (ref "R14") (pin "1") (pinfunction "1_1") (pintype "passive"))
      (node (ref "R15") (pin "2") (pinfunction "2_2") (pintype "passive"))
      (node (ref "R16") (pin "2") (pinfunction "2_2") (pintype "passive"))
    )
    (net (code "32") (name "Net-(L5-Pad1)") (class "Default")
      (node (ref "L5") (pin "1") (pinfunction "1_1") (pintype "passive"))
      (node (ref "L6") (pin "1") (pinfunction "1_1") (pintype "passive"))
      (node (ref "Y2") (pin "P1") (pinfunction "P1_P1") (pintype "bidirectional"))
    )
    (net (code "33") (name "Net-(LED1-PadA)") (class "Default")
      (node (ref "LED1") (pin "A") (pinfunction "A_A") (pintype "passive"))
      (node (ref "R10") (pin "1") (pinfunction "1_1") (pintype "passive"))
    )
    (net (code "34") (name "Net-(LED2-PadA)") (class "Default")
      (node (ref "LED2") (pin "A") (pinfunction "A_A") (pintype "passive"))
      (node (ref "R23") (pin "1") (pinfunction "1_1") (pintype "passive"))
    )
    (net (code "35") (name "Net-(Q2-D)") (class "Default")
      (node (ref "LED1") (pin "C") (pinfunction "C_C") (pintype "passive"))
      (node (ref "Q2") (pin "P3") (pinfunction "D_P3") (pintype "passive"))
    )
    (net (code "36") (name "Net-(Q3-D)") (class "Default")
      (node (ref "LED2") (pin "C") (pinfunction "C_C") (pintype "passive"))
      (node (ref "Q3") (pin "P3") (pinfunction "D_P3") (pintype "passive"))
    )
    (net (code "37") (name "Net-(R18-Pad2)") (class "Default")
      (node (ref "R18") (pin "2") (pinfunction "2_2") (pintype "passive"))
      (node (ref "R36") (pin "PW") (pinfunction "PW_PW") (pintype "passive"))
    )
    (net (code "38") (name "Net-(R35-Pad2)") (class "Default")
      (node (ref "R35") (pin "2") (pinfunction "2_2") (pintype "passive"))
      (node (ref "R42") (pin "P2") (pinfunction "P2_P2") (pintype "passive"))
    )
    (net (code "39") (name "Net-(R38-Pad2)") (class "Default")
      (node (ref "R38") (pin "2") (pinfunction "2_2") (pintype "passive"))
      (node (ref "R41") (pin "PW") (pinfunction "PW_PW") (pintype "passive"))
    )
    (net (code "40") (name "Net-(U1-FB)") (class "Default")
      (node (ref "C4") (pin "2") (pinfunction "2_2") (pintype "passive"))
      (node (ref "R7") (pin "1") (pinfunction "1_1") (pintype "passive"))
      (node (ref "R9") (pin "2") (pinfunction "2_2") (pintype "passive"))
      (node (ref "U1") (pin "P3") (pinfunction "FB_P3") (pintype "bidirectional"))
    )
    (net (code "41") (name "Net-(U1-SW)") (class "Default")
      (node (ref "L1") (pin "2") (pinfunction "2_2") (pintype "passive"))
      (node (ref "U1") (pin "P1") (pinfunction "SW_P1") (pintype "bidirectional"))
    )
    (net (code "42") (name "Net-(U1-VOUT)") (class "Default")
      (node (ref "C10") (pin "1") (pinfunction "1_1") (pintype "passive"))
      (node (ref "C4") (pin "1") (pinfunction "1_1") (pintype "passive"))
      (node (ref "C9") (pin "1") (pinfunction "1_1") (pintype "passive"))
      (node (ref "CS+") (pin "P$1") (pinfunction "P$1_P$1") (pintype "bidirectional"))
      (node (ref "L1") (pin "1") (pinfunction "1_1") (pintype "passive"))
      (node (ref "R13") (pin "1") (pinfunction "1_1") (pintype "passive"))
      (node (ref "R7") (pin "2") (pinfunction "2_2") (pintype "passive"))
      (node (ref "U1") (pin "P2") (pinfunction "VOUT_P2") (pintype "bidirectional"))
    )
    (net (code "43") (name "Net-(U2-BBOUT)") (class "Default")
      (node (ref "C33") (pin "2") (pinfunction "2_2") (pintype "passive"))
      (node (ref "U2") (pin "P5") (pinfunction "BBOUT_P5") (pintype "bidirectional"))
    )
    (net (code "44") (name "Net-(U2-CMPIN)") (class "Default")
      (node (ref "C33") (pin "1") (pinfunction "1_1") (pintype "passive"))
      (node (ref "U2") (pin "P6") (pinfunction "CMPIN_P6") (pintype "bidirectional"))
    )
    (net (code "45") (name "Net-(U2-LPFADJ)") (class "Default")
      (node (ref "R29") (pin "2") (pinfunction "2_2") (pintype "passive"))
      (node (ref "U2") (pin "P9") (pinfunction "LPFADJ_P9") (pintype "bidirectional"))
    )
    (net (code "46") (name "Net-(U2-PRATE)") (class "Default")
      (node (ref "R28") (pin "2") (pinfunction "2_2") (pintype "passive"))
      (node (ref "U2") (pin "P14") (pinfunction "PRATE_P14") (pintype "bidirectional"))
    )
    (net (code "47") (name "Net-(U2-PWIDTH)") (class "Default")
      (node (ref "R22") (pin "2") (pinfunction "2_2") (pintype "passive"))
      (node (ref "U2") (pin "P15") (pinfunction "PWIDTH_P15") (pintype "bidirectional"))
    )
    (net (code "48") (name "Net-(U2-REF)") (class "Default")
      (node (ref "R26") (pin "1") (pinfunction "1_1") (pintype "passive"))
      (node (ref "U2") (pin "P11") (pinfunction "REF_P11") (pintype "bidirectional"))
      (node (ref "U2") (pin "P13") (pinfunction "THLD1_P13") (pintype "bidirectional"))
    )
    (net (code "49") (name "Net-(U2-RFIO)") (class "Default")
      (node (ref "L5") (pin "2") (pinfunction "2_2") (pintype "passive"))
      (node (ref "U2") (pin "P20") (pinfunction "RFIO_P20") (pintype "bidirectional"))
    )
    (net (code "50") (name "Net-(U2-TXMOD)") (class "Default")
      (node (ref "R30") (pin "2") (pinfunction "2_2") (pintype "passive"))
      (node (ref "U2") (pin "P8") (pinfunction "TXMOD_P8") (pintype "bidirectional"))
    )
    (net (code "51") (name "Net-(U2-VCC1)") (class "Default")
      (node (ref "L7") (pin "2") (pinfunction "2_2") (pintype "passive"))
      (node (ref "U2") (pin "P2") (pinfunction "VCC1_P2") (pintype "bidirectional"))
    )
    (net (code "52") (name "Net-(U3-VCORE)") (class "Default")
      (node (ref "C16") (pin "2") (pinfunction "2_2") (pintype "passive"))
      (node (ref "U3") (pin "P18") (pinfunction "VCORE_P18") (pintype "bidirectional"))
    )
    (net (code "53") (name "Net-(U3-XIN)") (class "Default")
      (node (ref "C8") (pin "2") (pinfunction "2_2") (pintype "passive"))
      (node (ref "U3") (pin "P21") (pinfunction "XIN_P21") (pintype "bidirectional"))
      (node (ref "X3") (pin "2") (pinfunction "P2_2") (pintype "bidirectional"))
    )
    (net (code "54") (name "Net-(U3-XOUT)") (class "Default")
      (node (ref "C34") (pin "2") (pinfunction "2_2") (pintype "passive"))
      (node (ref "U3") (pin "P22") (pinfunction "XOUT_P22") (pintype "bidirectional"))
      (node (ref "X3") (pin "1") (pinfunction "P1_1") (pintype "bidirectional"))
    )
    (net (code "55") (name "Net-(U4A-CAP_PA1M)") (class "Default")
      (node (ref "C5") (pin "2") (pinfunction "2_2") (pintype "passive"))
      (node (ref "U4") (pin "P3") (pinfunction "CAP_PA1M_P3") (pintype "bidirectional"))
    )
    (net (code "56") (name "Net-(U4A-CAP_PA1P)") (class "Default")
      (node (ref "C5") (pin "1") (pinfunction "1_1") (pintype "passive"))
      (node (ref "U4") (pin "P2") (pinfunction "CAP_PA1P_P2") (pintype "bidirectional"))
    )
    (net (code "57") (name "Net-(U4A-CAP_PA2M)") (class "Default")
      (node (ref "C6") (pin "2") (pinfunction "2_2") (pintype "passive"))
      (node (ref "U4") (pin "P4") (pinfunction "CAP_PA2M_P4") (pintype "bidirectional"))
    )
    (net (code "58") (name "Net-(U4A-CAP_PA2P)") (class "Default")
      (node (ref "C6") (pin "1") (pinfunction "1_1") (pintype "passive"))
      (node (ref "U4") (pin "P5") (pinfunction "CAP_PA2P_P5") (pintype "bidirectional"))
    )
    (net (code "59") (name "Net-(U4A-CAP_PA3M)") (class "Default")
      (node (ref "C11") (pin "2") (pinfunction "2_2") (pintype "passive"))
      (node (ref "U4") (pin "P7") (pinfunction "CAP_PA3M_P7") (pintype "bidirectional"))
    )
    (net (code "60") (name "Net-(U4A-CAP_PA3P)") (class "Default")
      (node (ref "C11") (pin "1") (pinfunction "1_1") (pintype "passive"))
      (node (ref "U4") (pin "P6") (pinfunction "CAP_PA3P_P6") (pintype "bidirectional"))
    )
    (net (code "61") (name "Net-(U4A-CAP_PA4M)") (class "Default")
      (node (ref "C12") (pin "2") (pinfunction "2_2") (pintype "passive"))
      (node (ref "U4") (pin "P8") (pinfunction "CAP_PA4M_P8") (pintype "bidirectional"))
    )
    (net (code "62") (name "Net-(U4A-CAP_PA4P)") (class "Default")
      (node (ref "C12") (pin "1") (pinfunction "1_1") (pintype "passive"))
      (node (ref "U4") (pin "P9") (pinfunction "CAP_PA4P_P9") (pintype "bidirectional"))
    )
    (net (code "63") (name "Net-(U4A-CAP_PR1M)") (class "Default")
      (node (ref "C13") (pin "2") (pinfunction "2_2") (pintype "passive"))
      (node (ref "U4") (pin "P63") (pinfunction "CAP_PR1M_P63") (pintype "bidirectional"))
    )
    (net (code "64") (name "Net-(U4A-CAP_PR1P)") (class "Default")
      (node (ref "C13") (pin "1") (pinfunction "1_1") (pintype "passive"))
      (node (ref "U4") (pin "P64") (pinfunction "CAP_PR1P_P64") (pintype "bidirectional"))
    )
    (net (code "65") (name "Net-(U4A-CAP_PR2M)") (class "Default")
      (node (ref "C17") (pin "2") (pinfunction "2_2") (pintype "passive"))
      (node (ref "U4") (pin "P62") (pinfunction "CAP_PR2M_P62") (pintype "bidirectional"))
    )
    (net (code "66") (name "Net-(U4A-CAP_PR2P)") (class "Default")
      (node (ref "C17") (pin "1") (pinfunction "1_1") (pintype "passive"))
      (node (ref "U4") (pin "P61") (pinfunction "CAP_PR2P_P61") (pintype "bidirectional"))
    )
    (net (code "67") (name "Net-(U4A-CAP_PR3M)") (class "Default")
      (node (ref "C18") (pin "2") (pinfunction "2_2") (pintype "passive"))
      (node (ref "U4") (pin "P59") (pinfunction "CAP_PR3M_P59") (pintype "bidirectional"))
    )
    (net (code "68") (name "Net-(U4A-CAP_PR3P)") (class "Default")
      (node (ref "C18") (pin "1") (pinfunction "1_1") (pintype "passive"))
      (node (ref "U4") (pin "P60") (pinfunction "CAP_PR3P_P60") (pintype "bidirectional"))
    )
    (net (code "69") (name "Net-(U4A-CAP_PR4M)") (class "Default")
      (node (ref "C19") (pin "2") (pinfunction "2_2") (pintype "passive"))
      (node (ref "U4") (pin "P58") (pinfunction "CAP_PR4M_P58") (pintype "bidirectional"))
    )
    (net (code "70") (name "Net-(U4A-CAP_PR4P)") (class "Default")
      (node (ref "C19") (pin "1") (pinfunction "1_1") (pintype "passive"))
      (node (ref "U4") (pin "P57") (pinfunction "CAP_PR4P_P57") (pintype "bidirectional"))
    )
    (net (code "71") (name "Net-(U4B-ANT)") (class "Default")
      (node (ref "C29") (pin "1") (pinfunction "1_1") (pintype "passive"))
      (node (ref "L4") (pin "2") (pinfunction "2_2") (pintype "passive"))
      (node (ref "U4") (pin "P14") (pinfunction "ANT_P14") (pintype "bidirectional"))
    )
    (net (code "72") (name "Net-(U4B-OSCAIN)") (class "Default")
      (node (ref "U4") (pin "P28") (pinfunction "OSCAIN_P28") (pintype "bidirectional"))
      (node (ref "X1") (pin "P3") (pinfunction "P2_P3") (pintype "bidirectional"))
    )
    (net (code "73") (name "Net-(U4B-OSCAOUT)") (class "Default")
      (node (ref "U4") (pin "P29") (pinfunction "OSCAOUT_P29") (pintype "bidirectional"))
      (node (ref "X1") (pin "P1") (pinfunction "P1_P1") (pintype "bidirectional"))
    )
    (net (code "74") (name "Net-(U4B-OSCBIN)") (class "Default")
      (node (ref "U4") (pin "P20") (pinfunction "OSCBIN_P20") (pintype "bidirectional"))
      (node (ref "X2") (pin "P2") (pinfunction "P2_P2") (pintype "bidirectional"))
    )
    (net (code "75") (name "Net-(U4B-OSCBOUT)") (class "Default")
      (node (ref "U4") (pin "P19") (pinfunction "OSCBOUT_P19") (pintype "bidirectional"))
      (node (ref "X2") (pin "P1") (pinfunction "P1_P1") (pintype "bidirectional"))
    )
    (net (code "76") (name "Net-(U4B-R_INHIBIT)") (class "Default")
      (node (ref "R43") (pin "1") (pinfunction "1_1") (pintype "passive"))
      (node (ref "U4") (pin "P1") (pinfunction "R_INHIBIT_P1") (pintype "bidirectional"))
    )
    (net (code "77") (name "Net-(U4B-TCK)") (class "Default")
      (node (ref "TP2") (pin "P$1") (pinfunction "P$1_P$1") (pintype "bidirectional"))
      (node (ref "U4") (pin "P26") (pinfunction "TCK_P26") (pintype "bidirectional"))
    )
    (net (code "78") (name "Net-(U4B-TDI)") (class "Default")
      (node (ref "TP7") (pin "P$1") (pinfunction "P$1_P$1") (pintype "bidirectional"))
      (node (ref "U4") (pin "P23") (pinfunction "TDI_P23") (pintype "bidirectional"))
    )
    (net (code "79") (name "Net-(U4B-TDO)") (class "Default")
      (node (ref "TP6") (pin "P$1") (pinfunction "P$1_P$1") (pintype "bidirectional"))
      (node (ref "U4") (pin "P24") (pinfunction "TDO_P24") (pintype "bidirectional"))
    )
    (net (code "80") (name "Net-(U4B-TMS)") (class "Default")
      (node (ref "TP5") (pin "P$1") (pinfunction "P$1_P$1") (pintype "bidirectional"))
      (node (ref "U4") (pin "P25") (pinfunction "TMS_P25") (pintype "bidirectional"))
    )
    (net (code "81") (name "Net-(U4B-VCORE)") (class "Default")
      (node (ref "C21") (pin "1") (pinfunction "1_1") (pintype "passive"))
      (node (ref "U4") (pin "P31") (pinfunction "VCORE_P31") (pintype "bidirectional"))
    )
    (net (code "82") (name "Net-(U4B-VDDA)") (class "Default")
      (node (ref "C22") (pin "1") (pinfunction "1_1") (pintype "passive"))
      (node (ref "U4") (pin "P30") (pinfunction "VDDA_P30") (pintype "bidirectional"))
    )
    (net (code "83") (name "Net-(U4B-VDDPA)") (class "Default")
      (node (ref "C23") (pin "1") (pinfunction "1_1") (pintype "passive"))
      (node (ref "U4") (pin "P10") (pinfunction "VDDPA_P10") (pintype "bidirectional"))
    )
    (net (code "84") (name "Net-(U4B-VOSC)") (class "Default")
      (node (ref "C20") (pin "1") (pinfunction "1_1") (pintype "passive"))
      (node (ref "U4") (pin "P32") (pinfunction "VOSC_P32") (pintype "bidirectional"))
    )
    (net (code "85") (name "Net-(U4B-VPP)") (class "Default")
      (node (ref "TP8") (pin "P$1") (pinfunction "P$1_P$1") (pintype "bidirectional"))
      (node (ref "U4") (pin "P54") (pinfunction "VPP_P54") (pintype "bidirectional"))
    )
    (net (code "86") (name "Net-(U4B-VPRIME)") (class "Default")
      (node (ref "C24") (pin "1") (pinfunction "1_1") (pintype "passive"))
      (node (ref "U4") (pin "P56") (pinfunction "VPRIME_P56") (pintype "bidirectional"))
    )
    (net (code "87") (name "Net-(U4B-VSUPPLY)") (class "Default")
      (node (ref "C25") (pin "1") (pinfunction "1_1") (pintype "passive"))
      (node (ref "C26") (pin "1") (pinfunction "1_1") (pintype "passive"))
      (node (ref "L2") (pin "2") (pinfunction "2_2") (pintype "passive"))
      (node (ref "U4") (pin "P65") (pinfunction "VSUPPLY_P65") (pintype "bidirectional"))
    )
    (net (code "88") (name "Net-(U5-IN+)") (class "Default")
      (node (ref "L3") (pin "1") (pinfunction "1_1") (pintype "passive"))
      (node (ref "R14") (pin "2") (pinfunction "2_2") (pintype "passive"))
      (node (ref "U5") (pin "P1") (pinfunction "IN+_P1") (pintype "bidirectional"))
    )
    (net (code "89") (name "Net-(U5-IN-)") (class "Default")
      (node (ref "R17") (pin "1") (pinfunction "1_1") (pintype "passive"))
      (node (ref "R36") (pin "P2") (pinfunction "P2_P2") (pintype "passive"))
      (node (ref "U5") (pin "P3") (pinfunction "IN-_P3") (pintype "bidirectional"))
    )
    (net (code "90") (name "Net-(U5-OUT)") (class "Default")
      (node (ref "C39") (pin "1") (pinfunction "1_1") (pintype "passive"))
      (node (ref "R17") (pin "2") (pinfunction "2_2") (pintype "passive"))
      (node (ref "TP1") (pin "P$1") (pinfunction "P$1_P$1") (pintype "bidirectional"))
      (node (ref "U5") (pin "P4") (pinfunction "OUT_P4") (pintype "bidirectional"))
    )
    (net (code "91") (name "Net-(U6-IN+)") (class "Default")
      (node (ref "R20") (pin "1") (pinfunction "1_1") (pintype "passive"))
      (node (ref "R21") (pin "2") (pinfunction "2_2") (pintype "passive"))
      (node (ref "U6") (pin "P1") (pinfunction "IN+_P1") (pintype "bidirectional"))
    )
    (net (code "92") (name "Net-(U6-IN-)") (class "Default")
      (node (ref "RF") (pin "1") (pinfunction "1_1") (pintype "passive"))
      (node (ref "RI1") (pin "2") (pinfunction "2_2") (pintype "passive"))
      (node (ref "RI2") (pin "2") (pinfunction "2_2") (pintype "passive"))
      (node (ref "U6") (pin "P3") (pinfunction "IN-_P3") (pintype "bidirectional"))
    )
    (net (code "93") (name "Net-(U7A-IN+)") (class "Default")
      (node (ref "R39") (pin "P2") (pinfunction "P2_P2") (pintype "passive"))
      (node (ref "R40") (pin "1") (pinfunction "1_1") (pintype "passive"))
      (node (ref "U7") (pin "P3") (pinfunction "IN+_P3") (pintype "bidirectional"))
    )
    (net (code "94") (name "Net-(U7A-IN-)") (class "Default")
      (node (ref "R35") (pin "1") (pinfunction "1_1") (pintype "passive"))
      (node (ref "U7") (pin "P1") (pinfunction "OUT_P1") (pintype "bidirectional"))
      (node (ref "U7") (pin "P2") (pinfunction "IN-_P2") (pintype "bidirectional"))
    )
    (net (code "95") (name "Net-(U7B-IN+)") (class "Default")
      (node (ref "C39") (pin "2") (pinfunction "2_2") (pintype "passive"))
      (node (ref "R42") (pin "PW") (pinfunction "PW_PW") (pintype "passive"))
      (node (ref "TP9") (pin "P$1") (pinfunction "P$1_P$1") (pintype "bidirectional"))
      (node (ref "U7") (pin "P5") (pinfunction "IN+_P5") (pintype "bidirectional"))
    )
    (net (code "96") (name "Net-(U7B-IN-)") (class "Default")
      (node (ref "R37") (pin "1") (pinfunction "1_1") (pintype "passive"))
      (node (ref "R41") (pin "P2") (pinfunction "P2_P2") (pintype "passive"))
      (node (ref "U7") (pin "P6") (pinfunction "IN-_P6") (pintype "bidirectional"))
    )
    (net (code "97") (name "RST") (class "Default")
      (node (ref "J1") (pin "P10") (pinfunction "11_P10") (pintype "bidirectional"))
      (node (ref "R19") (pin "1") (pinfunction "1_1") (pintype "passive"))
      (node (ref "U3") (pin "P12") (pinfunction "RST_P12") (pintype "bidirectional"))
    )
    (net (code "98") (name "RXDATA") (class "Default")
      (node (ref "R34") (pin "2") (pinfunction "2_2") (pintype "passive"))
      (node (ref "TP11") (pin "P$1") (pinfunction "P$1_P$1") (pintype "bidirectional"))
      (node (ref "U2") (pin "P7") (pinfunction "RXDATA_P7") (pintype "bidirectional"))
      (node (ref "U3") (pin "P16") (pinfunction "P1.6/TA0.0/UCBSDA/MOSI_P16") (pintype "bidirectional"))
    )
    (net (code "99") (name "TCK") (class "Default")
      (node (ref "J1") (pin "P7") (pinfunction "7_P7") (pintype "bidirectional"))
      (node (ref "Q2") (pin "P1") (pinfunction "G_P1") (pintype "passive"))
      (node (ref "U3") (pin "P10") (pinfunction "TCK_P10") (pintype "bidirectional"))
    )
    (net (code "100") (name "TDI") (class "Default")
      (node (ref "J1") (pin "P3") (pinfunction "3_P3") (pintype "bidirectional"))
      (node (ref "Q3") (pin "P1") (pinfunction "G_P1") (pintype "passive"))
      (node (ref "U3") (pin "P8") (pinfunction "TDI_P8") (pintype "bidirectional"))
    )
    (net (code "101") (name "TDO") (class "Default")
      (node (ref "J1") (pin "P1") (pinfunction "1_P1") (pintype "bidirectional"))
      (node (ref "U3") (pin "P7") (pinfunction "TDO_P7") (pintype "bidirectional"))
    )
    (net (code "102") (name "TEST") (class "Default")
      (node (ref "J1") (pin "P8") (pinfunction "8_P8") (pintype "bidirectional"))
      (node (ref "U3") (pin "P11") (pinfunction "TEST_P11") (pintype "bidirectional"))
    )
    (net (code "103") (name "TMS") (class "Default")
      (node (ref "J1") (pin "P5") (pinfunction "5_P5") (pintype "bidirectional"))
      (node (ref "U3") (pin "P9") (pinfunction "TMS_P9") (pintype "bidirectional"))
    )
    (net (code "104") (name "TXMOD") (class "Default")
      (node (ref "R30") (pin "1") (pinfunction "1_1") (pintype "passive"))
      (node (ref "R33") (pin "2") (pinfunction "2_2") (pintype "passive"))
      (node (ref "TP10") (pin "P$1") (pinfunction "P$1_P$1") (pintype "bidirectional"))
      (node (ref "U3") (pin "P3") (pinfunction "P1.2/TA1.1/A2_P3") (pintype "bidirectional"))
    )
    (net (code "105") (name "UC_RX") (class "Default")
      (node (ref "SV1") (pin "10") (pinfunction "10_10") (pintype "passive"))
      (node (ref "U4") (pin "P38") (pinfunction "UCRX_P38") (pintype "bidirectional"))
    )
    (net (code "106") (name "UC_TX") (class "Default")
      (node (ref "SV1") (pin "9") (pinfunction "9_9") (pintype "passive"))
      (node (ref "U4") (pin "P37") (pinfunction "UCTX_P37") (pintype "bidirectional"))
    )
    (net (code "107") (name "VCC") (class "Default")
      (node (ref "C3") (pin "1") (pinfunction "1_1") (pintype "passive"))
      (node (ref "C32") (pin "1") (pinfunction "1_1") (pintype "passive"))
      (node (ref "C7") (pin "1") (pinfunction "1_1") (pintype "passive"))
      (node (ref "D1") (pin "C") (pinfunction "C_C") (pintype "passive"))
      (node (ref "R11") (pin "2") (pinfunction "2_2") (pintype "passive"))
      (node (ref "R3") (pin "2") (pinfunction "2_2") (pintype "passive"))
      (node (ref "R5") (pin "2") (pinfunction "2_2") (pintype "passive"))
      (node (ref "RS+") (pin "P$1") (pinfunction "P$1_P$1") (pintype "bidirectional"))
      (node (ref "U1") (pin "P4") (pinfunction "EN_P4") (pintype "bidirectional"))
      (node (ref "U1") (pin "P5") (pinfunction "VIN_P5") (pintype "bidirectional"))
    )
    (net (code "108") (name "VCC_SENSE") (class "Default")
      (node (ref "R11") (pin "1") (pinfunction "1_1") (pintype "passive"))
      (node (ref "R12") (pin "2") (pinfunction "2_2") (pintype "passive"))
      (node (ref "U3") (pin "P4") (pinfunction "P1.3/TA1.2/A3_P4") (pintype "bidirectional"))
    )
    (net (code "109") (name "VTEST") (class "Default")
      (node (ref "C1") (pin "2") (pinfunction "2_2") (pintype "passive"))
      (node (ref "C2") (pin "2") (pinfunction "2_2") (pintype "passive"))
      (node (ref "HVS") (pin "P$1") (pinfunction "P$1_P$1") (pintype "bidirectional"))
      (node (ref "R1") (pin "2") (pinfunction "2_2") (pintype "passive"))
      (node (ref "R8") (pin "1") (pinfunction "1_1") (pintype "passive"))
      (node (ref "RI1") (pin "1") (pinfunction "1_1") (pintype "passive"))
    )
    (net (code "110") (name "V_SENSE") (class "Default")
      (node (ref "RF") (pin "2") (pinfunction "2_2") (pintype "passive"))
      (node (ref "TP3") (pin "P$1") (pinfunction "P$1_P$1") (pintype "bidirectional"))
      (node (ref "U3") (pin "P5") (pinfunction "P1.4/TB0.1/A4_P5") (pintype "bidirectional"))
      (node (ref "U4") (pin "P17") (pinfunction "A3_P17") (pintype "bidirectional"))
      (node (ref "U6") (pin "P4") (pinfunction "OUT_P4") (pintype "bidirectional"))
    )
    (net (code "111") (name "unconnected-(J1-4-PadP4)") (class "Default")
      (node (ref "J1") (pin "P4") (pinfunction "4_P4") (pintype "bidirectional"))
    )
    (net (code "112") (name "unconnected-(J1-6-PadP6)") (class "Default")
      (node (ref "J1") (pin "P6") (pinfunction "6_P6") (pintype "bidirectional"))
    )
    (net (code "113") (name "unconnected-(R36-PadP1)") (class "Default")
      (node (ref "R36") (pin "P1") (pinfunction "P1_P1") (pintype "passive"))
    )
    (net (code "114") (name "unconnected-(R39-PadP1)") (class "Default")
      (node (ref "R39") (pin "P1") (pinfunction "P1_P1") (pintype "passive"))
    )
    (net (code "115") (name "unconnected-(R41-PadP1)") (class "Default")
      (node (ref "R41") (pin "P1") (pinfunction "P1_P1") (pintype "passive"))
    )
    (net (code "116") (name "unconnected-(R42-PadP1)") (class "Default")
      (node (ref "R42") (pin "P1") (pinfunction "P1_P1") (pintype "passive"))
    )
    (net (code "117") (name "unconnected-(U2-PKDET-PadP4)") (class "Default")
      (node (ref "U2") (pin "P4") (pinfunction "PKDET_P4") (pintype "bidirectional"))
    )
    (net (code "118") (name "unconnected-(U2-THLD2-PadP12)") (class "Default")
      (node (ref "U2") (pin "P12") (pinfunction "THLD2_P12") (pintype "bidirectional"))
    )
    (net (code "119") (name "unconnected-(U4B-LNA_EN-PadP11)") (class "Default")
      (node (ref "U4") (pin "P11") (pinfunction "LNA_EN_P11") (pintype "bidirectional"))
    )
    (net (code "120") (name "unconnected-(U4B-RADIOTX-PadP12)") (class "Default")
      (node (ref "U4") (pin "P12") (pinfunction "RADIOTX_P12") (pintype "bidirectional"))
    )
    (net (code "121") (name "unconnected-(U4B-RADIOTXN-PadP13)") (class "Default")
      (node (ref "U4") (pin "P13") (pinfunction "RADIOTXN_P13") (pintype "bidirectional"))
    )
    (net (code "122") (name "unconnected-(U4B-VBGAP-PadP21)") (class "Default")
      (node (ref "U4") (pin "P21") (pinfunction "VBGAP_P21") (pintype "bidirectional"))
    )
    (net (code "123") (name "unconnected-(U4C-A0-PadP15)") (class "Default")
      (node (ref "U4") (pin "P15") (pinfunction "A0_P15") (pintype "bidirectional"))
    )
    (net (code "124") (name "unconnected-(U4C-A1-PadP16)") (class "Default")
      (node (ref "U4") (pin "P16") (pinfunction "A1_P16") (pintype "bidirectional"))
    )
    (net (code "125") (name "unconnected-(U4C-DP0-PadP36)") (class "Default")
      (node (ref "U4") (pin "P36") (pinfunction "DP0_P36") (pintype "bidirectional"))
    )
    (net (code "126") (name "unconnected-(U4C-DP1-PadP48)") (class "Default")
      (node (ref "U4") (pin "P48") (pinfunction "DP1_P48") (pintype "bidirectional"))
    )
    (net (code "127") (name "unconnected-(U4C-DP2-PadP34)") (class "Default")
      (node (ref "U4") (pin "P34") (pinfunction "DP2_P34") (pintype "bidirectional"))
    )
    (net (code "128") (name "unconnected-(U4C-DP3-PadP33)") (class "Default")
      (node (ref "U4") (pin "P33") (pinfunction "DP3_P33") (pintype "bidirectional"))
    )
    (net (code "129") (name "unconnected-(U4C-DP4-PadP27)") (class "Default")
      (node (ref "U4") (pin "P27") (pinfunction "DP4_P27") (pintype "bidirectional"))
    )
    (net (code "130") (name "unconnected-(U4C-MMISO-PadP39)") (class "Default")
      (node (ref "U4") (pin "P39") (pinfunction "MMISO_P39") (pintype "bidirectional"))
    )
    (net (code "131") (name "unconnected-(U4C-MMOSI-PadP41)") (class "Default")
      (node (ref "U4") (pin "P41") (pinfunction "MMOSI_P41") (pintype "bidirectional"))
    )
    (net (code "132") (name "unconnected-(U4C-MSCK-PadP43)") (class "Default")
      (node (ref "U4") (pin "P43") (pinfunction "MSCK_P43") (pintype "bidirectional"))
    )
    (net (code "133") (name "unconnected-(U4C-MSS0-PadP47)") (class "Default")
      (node (ref "U4") (pin "P47") (pinfunction "MSS0_P47") (pintype "bidirectional"))
    )
    (net (code "134") (name "unconnected-(U4C-MSS1-PadP46)") (class "Default")
      (node (ref "U4") (pin "P46") (pinfunction "MSS1_P46") (pintype "bidirectional"))
    )
    (net (code "135") (name "unconnected-(U4C-PWM0-PadP49)") (class "Default")
      (node (ref "U4") (pin "P49") (pinfunction "PWM0_P49") (pintype "bidirectional"))
    )
    (net (code "136") (name "unconnected-(U4C-SCLK-PadP52)") (class "Default")
      (node (ref "U4") (pin "P52") (pinfunction "SCLK_P52") (pintype "bidirectional"))
    )
    (net (code "137") (name "unconnected-(U4C-SMISO-PadP50)") (class "Default")
      (node (ref "U4") (pin "P50") (pinfunction "SMISO_P50") (pintype "bidirectional"))
    )
    (net (code "138") (name "unconnected-(U4C-SMOSI-PadP51)") (class "Default")
      (node (ref "U4") (pin "P51") (pinfunction "SMOSI_P51") (pintype "bidirectional"))
    )
    (net (code "139") (name "unconnected-(U4C-SSS-PadP53)") (class "Default")
      (node (ref "U4") (pin "P53") (pinfunction "SSS_P53") (pintype "bidirectional"))
    )
  )
)
